# ucar.net
KiCad netlist of a schematic drawn in EAGLE
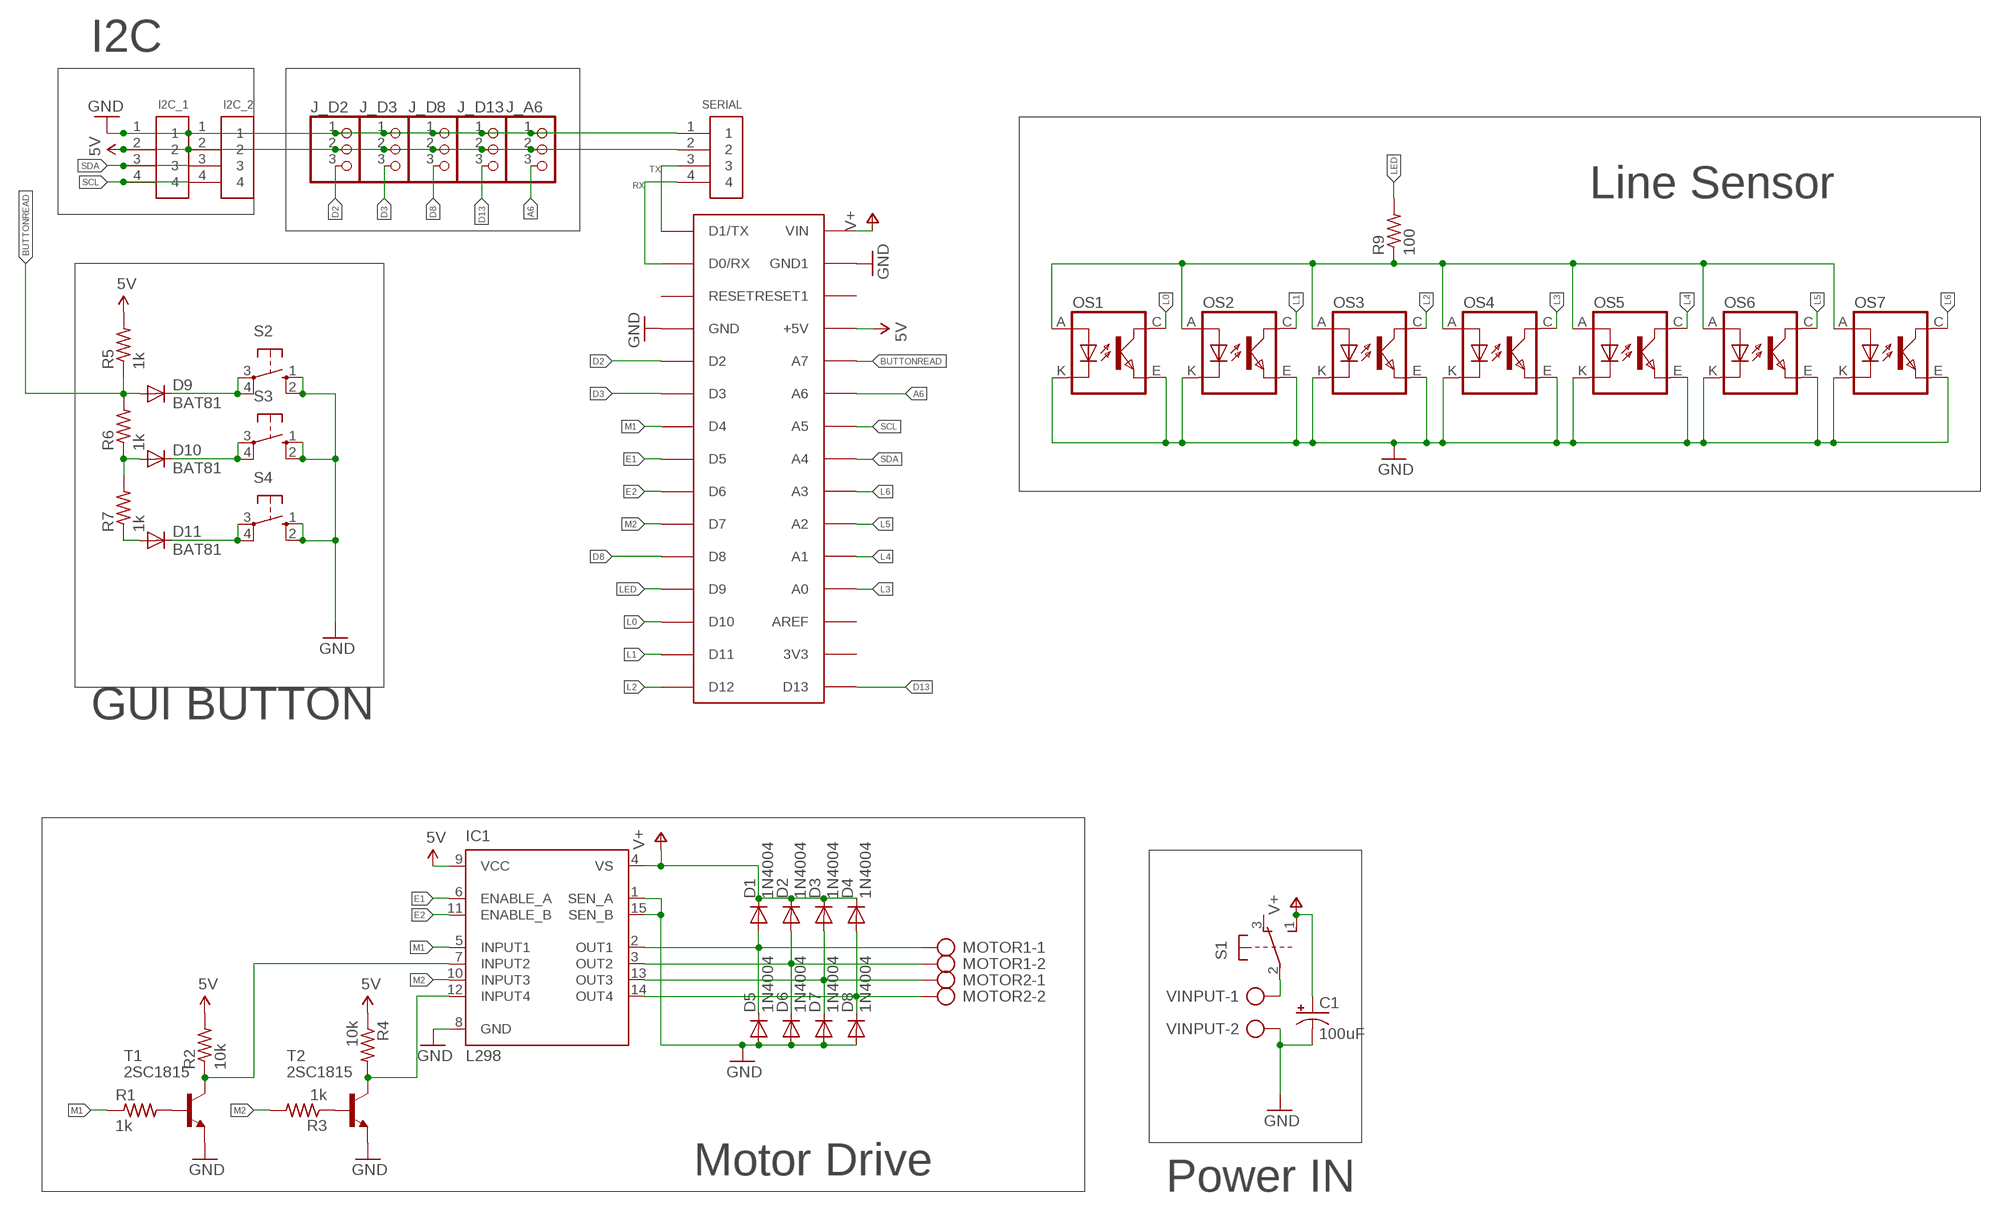
[diagram p0: schematic, sheet 1]

(export (version "E")
  (design (tool "Eeschema 10.0.6"))
  (components
    (comp (ref "C1")
      (value "100uF")
      (footprint "eagle-import:E2,5-6")
      (libsource (lib "eagle-import") (part "CPOL-USE2.5-6"))
    )
    (comp (ref "D1")
      (value "1N4004")
      (footprint "eagle-import:DO41-10")
      (libsource (lib "eagle-import") (part "1N4004"))
    )
    (comp (ref "D2")
      (value "1N4004")
      (footprint "eagle-import:DO41-10")
      (libsource (lib "eagle-import") (part "1N4004"))
    )
    (comp (ref "D3")
      (value "1N4004")
      (footprint "eagle-import:DO41-10")
      (libsource (lib "eagle-import") (part "1N4004"))
    )
    (comp (ref "D4")
      (value "1N4004")
      (footprint "eagle-import:DO41-10")
      (libsource (lib "eagle-import") (part "1N4004"))
    )
    (comp (ref "D5")
      (value "1N4004")
      (footprint "eagle-import:DO41-10")
      (libsource (lib "eagle-import") (part "1N4004"))
    )
    (comp (ref "D6")
      (value "1N4004")
      (footprint "eagle-import:DO41-10")
      (libsource (lib "eagle-import") (part "1N4004"))
    )
    (comp (ref "D7")
      (value "1N4004")
      (footprint "eagle-import:DO41-10")
      (libsource (lib "eagle-import") (part "1N4004"))
    )
    (comp (ref "D8")
      (value "1N4004")
      (footprint "eagle-import:DO41-10")
      (libsource (lib "eagle-import") (part "1N4004"))
    )
    (comp (ref "D9")
      (value "BAT81")
      (footprint "eagle-import:DO34-7")
      (libsource (lib "eagle-import") (part "BAT81"))
    )
    (comp (ref "D10")
      (value "BAT81")
      (footprint "eagle-import:DO34-7")
      (libsource (lib "eagle-import") (part "BAT81"))
    )
    (comp (ref "D11")
      (value "BAT81")
      (footprint "eagle-import:DO34-7")
      (libsource (lib "eagle-import") (part "BAT81"))
    )
    (comp (ref "I2C_1")
      (value "1X4-BIG")
      (footprint "eagle-import:1X04-BIG")
      (libsource (lib "eagle-import") (part "1X4-BIG"))
    )
    (comp (ref "I2C_2")
      (value "1X4-BIG")
      (footprint "eagle-import:1X04-BIG")
      (libsource (lib "eagle-import") (part "1X4-BIG"))
    )
    (comp (ref "IC1")
      (value "L298")
      (footprint "eagle-import:MULTIWATT-15")
      (fields (field (name "MPN") "L298N"))
      (libsource (lib "eagle-import") (part "L298"))
    )
    (comp (ref "J_A6")
      (value "PINHD-1X3")
      (footprint "eagle-import:1X03")
      (libsource (lib "eagle-import") (part "PINHD-1X3"))
    )
    (comp (ref "J_D2")
      (value "PINHD-1X3")
      (footprint "eagle-import:1X03")
      (libsource (lib "eagle-import") (part "PINHD-1X3"))
    )
    (comp (ref "J_D3")
      (value "PINHD-1X3")
      (footprint "eagle-import:1X03")
      (libsource (lib "eagle-import") (part "PINHD-1X3"))
    )
    (comp (ref "J_D8")
      (value "PINHD-1X3")
      (footprint "eagle-import:1X03")
      (libsource (lib "eagle-import") (part "PINHD-1X3"))
    )
    (comp (ref "J_D13")
      (value "PINHD-1X3")
      (footprint "eagle-import:1X03")
      (libsource (lib "eagle-import") (part "PINHD-1X3"))
    )
    (comp (ref "MOTOR1")
      (value "AK500/2")
      (footprint "eagle-import:AK500_2")
      (libsource (lib "eagle-import") (part "AK500/2"))
    )
    (comp (ref "MOTOR2")
      (value "AK500/2")
      (footprint "eagle-import:AK500_2")
      (libsource (lib "eagle-import") (part "AK500/2"))
    )
    (comp (ref "OS1")
      (value "TCRT5000")
      (footprint "eagle-import:TCRT5000")
      (libsource (lib "eagle-import") (part "TCRT5000"))
    )
    (comp (ref "OS2")
      (value "TCRT5000")
      (footprint "eagle-import:TCRT5000")
      (libsource (lib "eagle-import") (part "TCRT5000"))
    )
    (comp (ref "OS3")
      (value "TCRT5000")
      (footprint "eagle-import:TCRT5000")
      (libsource (lib "eagle-import") (part "TCRT5000"))
    )
    (comp (ref "OS4")
      (value "TCRT5000")
      (footprint "eagle-import:TCRT5000")
      (libsource (lib "eagle-import") (part "TCRT5000"))
    )
    (comp (ref "OS5")
      (value "TCRT5000")
      (footprint "eagle-import:TCRT5000")
      (libsource (lib "eagle-import") (part "TCRT5000"))
    )
    (comp (ref "OS6")
      (value "TCRT5000")
      (footprint "eagle-import:TCRT5000")
      (libsource (lib "eagle-import") (part "TCRT5000"))
    )
    (comp (ref "OS7")
      (value "TCRT5000")
      (footprint "eagle-import:TCRT5000")
      (libsource (lib "eagle-import") (part "TCRT5000"))
    )
    (comp (ref "R1")
      (value "1k")
      (footprint "eagle-import:0207_7")
      (libsource (lib "eagle-import") (part "R-US_0207/7"))
    )
    (comp (ref "R2")
      (value "10k")
      (footprint "eagle-import:0207_7")
      (libsource (lib "eagle-import") (part "R-US_0207/7"))
    )
    (comp (ref "R3")
      (value "1k")
      (footprint "eagle-import:0207_7")
      (libsource (lib "eagle-import") (part "R-US_0207/7"))
    )
    (comp (ref "R4")
      (value "10k")
      (footprint "eagle-import:0207_7")
      (libsource (lib "eagle-import") (part "R-US_0207/7"))
    )
    (comp (ref "R5")
      (value "1k")
      (footprint "eagle-import:0207_7")
      (libsource (lib "eagle-import") (part "resistor_R-US_0207/7"))
    )
    (comp (ref "R6")
      (value "1k")
      (footprint "eagle-import:0207_7")
      (libsource (lib "eagle-import") (part "resistor_R-US_0207/7"))
    )
    (comp (ref "R7")
      (value "1k")
      (footprint "eagle-import:0207_7")
      (libsource (lib "eagle-import") (part "resistor_R-US_0207/7"))
    )
    (comp (ref "R9")
      (value "100")
      (footprint "eagle-import:0204_5")
      (libsource (lib "eagle-import") (part "R-US_0204/5"))
    )
    (comp (ref "S1")
      (value "9077-2")
      (footprint "eagle-import:9077-2")
      (libsource (lib "eagle-import") (part "9077-2"))
    )
    (comp (ref "S2")
      (value "10-XX")
      (footprint "eagle-import:B3F-10XX")
      (fields (field (name "MPN") "B3F-1000"))
      (libsource (lib "eagle-import") (part "10-XX"))
    )
    (comp (ref "S3")
      (value "10-XX")
      (footprint "eagle-import:B3F-10XX")
      (fields (field (name "MPN") "B3F-1000"))
      (libsource (lib "eagle-import") (part "10-XX"))
    )
    (comp (ref "S4")
      (value "10-XX")
      (footprint "eagle-import:B3F-10XX")
      (fields (field (name "MPN") "B3F-1000"))
      (libsource (lib "eagle-import") (part "10-XX"))
    )
    (comp (ref "SERIAL")
      (value "1X4-BIG")
      (footprint "eagle-import:1X04-BIG")
      (libsource (lib "eagle-import") (part "1X4-BIG"))
    )
    (comp (ref "T1")
      (value "2SC1815")
      (footprint "eagle-import:TO92-ECB")
      (libsource (lib "eagle-import") (part "2SC1815"))
    )
    (comp (ref "T2")
      (value "2SC1815")
      (footprint "eagle-import:TO92-ECB")
      (libsource (lib "eagle-import") (part "2SC1815"))
    )
    (comp (ref "U$1")
      (value "ARDUINONANO")
      (footprint "eagle-import:PDIP-32")
      (libsource (lib "eagle-import") (part "ARDUINONANO"))
    )
    (comp (ref "VINPUT")
      (value "AK500/2")
      (footprint "eagle-import:AK500_2")
      (libsource (lib "eagle-import") (part "AK500/2"))
    )
  )
  (nets
    (net (code "1") (name "/RX") (class "Default")
      (node (ref "SERIAL") (pin "4") (pinfunction "4_4") (pintype "bidirectional"))
      (node (ref "U$1") (pin "D0/RX") (pinfunction "D0/RX_D0/RX") (pintype "bidirectional"))
    )
    (net (code "2") (name "/TX") (class "Default")
      (node (ref "SERIAL") (pin "3") (pinfunction "3_3") (pintype "bidirectional"))
      (node (ref "U$1") (pin "D1/TX") (pinfunction "D1/TX_D1/TX") (pintype "bidirectional"))
    )
    (net (code "3") (name "5V") (class "Default")
      (node (ref "I2C_1") (pin "2") (pinfunction "2_2") (pintype "bidirectional"))
      (node (ref "I2C_2") (pin "2") (pinfunction "2_2") (pintype "bidirectional"))
      (node (ref "IC1") (pin "9") (pinfunction "VCC_9") (pintype "power_in"))
      (node (ref "J_A6") (pin "2") (pinfunction "2_2") (pintype "passive"))
      (node (ref "J_D13") (pin "2") (pinfunction "2_2") (pintype "passive"))
      (node (ref "J_D2") (pin "2") (pinfunction "2_2") (pintype "passive"))
      (node (ref "J_D3") (pin "2") (pinfunction "2_2") (pintype "passive"))
      (node (ref "J_D8") (pin "2") (pinfunction "2_2") (pintype "passive"))
      (node (ref "R2") (pin "2") (pinfunction "2_2") (pintype "passive"))
      (node (ref "R4") (pin "1") (pinfunction "1_1") (pintype "passive"))
      (node (ref "R5") (pin "2") (pinfunction "2_2") (pintype "passive"))
      (node (ref "SERIAL") (pin "2") (pinfunction "2_2") (pintype "bidirectional"))
      (node (ref "U$1") (pin "+5V") (pinfunction "+5V_+5V") (pintype "bidirectional"))
    )
    (net (code "4") (name "A6") (class "Default")
      (node (ref "J_A6") (pin "3") (pinfunction "3_3") (pintype "passive"))
      (node (ref "U$1") (pin "A6") (pinfunction "A6_A6") (pintype "bidirectional"))
    )
    (net (code "5") (name "BUTTONREAD") (class "Default")
      (node (ref "D9") (pin "A") (pinfunction "A_A") (pintype "passive"))
      (node (ref "R5") (pin "1") (pinfunction "1_1") (pintype "passive"))
      (node (ref "R6") (pin "2") (pinfunction "2_2") (pintype "passive"))
      (node (ref "U$1") (pin "A7") (pinfunction "A7_A7") (pintype "bidirectional"))
    )
    (net (code "6") (name "D2") (class "Default")
      (node (ref "J_D2") (pin "3") (pinfunction "3_3") (pintype "passive"))
      (node (ref "U$1") (pin "D2") (pinfunction "D2_D2") (pintype "bidirectional"))
    )
    (net (code "7") (name "D3") (class "Default")
      (node (ref "J_D3") (pin "3") (pinfunction "3_3") (pintype "passive"))
      (node (ref "U$1") (pin "D3") (pinfunction "D3_D3") (pintype "bidirectional"))
    )
    (net (code "8") (name "D8") (class "Default")
      (node (ref "J_D8") (pin "3") (pinfunction "3_3") (pintype "passive"))
      (node (ref "U$1") (pin "D8") (pinfunction "D8_D8") (pintype "bidirectional"))
    )
    (net (code "9") (name "D13") (class "Default")
      (node (ref "J_D13") (pin "3") (pinfunction "3_3") (pintype "passive"))
      (node (ref "U$1") (pin "D13") (pinfunction "D13_D13") (pintype "bidirectional"))
    )
    (net (code "10") (name "E1") (class "Default")
      (node (ref "IC1") (pin "6") (pinfunction "ENABLE_A_6") (pintype "input"))
      (node (ref "U$1") (pin "D5") (pinfunction "D5_D5") (pintype "bidirectional"))
    )
    (net (code "11") (name "E2") (class "Default")
      (node (ref "IC1") (pin "11") (pinfunction "ENABLE_B_11") (pintype "input"))
      (node (ref "U$1") (pin "D6") (pinfunction "D6_D6") (pintype "bidirectional"))
    )
    (net (code "12") (name "GND") (class "Default")
      (node (ref "C1") (pin "-") (pinfunction "-_-") (pintype "passive"))
      (node (ref "D5") (pin "A") (pinfunction "A_A") (pintype "passive"))
      (node (ref "D6") (pin "A") (pinfunction "A_A") (pintype "passive"))
      (node (ref "D7") (pin "A") (pinfunction "A_A") (pintype "passive"))
      (node (ref "D8") (pin "A") (pinfunction "A_A") (pintype "passive"))
      (node (ref "I2C_1") (pin "1") (pinfunction "1_1") (pintype "bidirectional"))
      (node (ref "I2C_2") (pin "1") (pinfunction "1_1") (pintype "bidirectional"))
      (node (ref "IC1") (pin "1") (pinfunction "SEN_A_1") (pintype "input"))
      (node (ref "IC1") (pin "15") (pinfunction "SEN_B_15") (pintype "input"))
      (node (ref "IC1") (pin "8") (pinfunction "GND_8") (pintype "power_in"))
      (node (ref "J_A6") (pin "1") (pinfunction "1_1") (pintype "passive"))
      (node (ref "J_D13") (pin "1") (pinfunction "1_1") (pintype "passive"))
      (node (ref "J_D2") (pin "1") (pinfunction "1_1") (pintype "passive"))
      (node (ref "J_D3") (pin "1") (pinfunction "1_1") (pintype "passive"))
      (node (ref "J_D8") (pin "1") (pinfunction "1_1") (pintype "passive"))
      (node (ref "OS1") (pin "E") (pinfunction "EMITTER_E") (pintype "passive"))
      (node (ref "OS1") (pin "K") (pinfunction "CATHODE_K") (pintype "passive"))
      (node (ref "OS2") (pin "E") (pinfunction "EMITTER_E") (pintype "passive"))
      (node (ref "OS2") (pin "K") (pinfunction "CATHODE_K") (pintype "passive"))
      (node (ref "OS3") (pin "E") (pinfunction "EMITTER_E") (pintype "passive"))
      (node (ref "OS3") (pin "K") (pinfunction "CATHODE_K") (pintype "passive"))
      (node (ref "OS4") (pin "E") (pinfunction "EMITTER_E") (pintype "passive"))
      (node (ref "OS4") (pin "K") (pinfunction "CATHODE_K") (pintype "passive"))
      (node (ref "OS5") (pin "E") (pinfunction "EMITTER_E") (pintype "passive"))
      (node (ref "OS5") (pin "K") (pinfunction "CATHODE_K") (pintype "passive"))
      (node (ref "OS6") (pin "E") (pinfunction "EMITTER_E") (pintype "passive"))
      (node (ref "OS6") (pin "K") (pinfunction "CATHODE_K") (pintype "passive"))
      (node (ref "OS7") (pin "E") (pinfunction "EMITTER_E") (pintype "passive"))
      (node (ref "OS7") (pin "K") (pinfunction "CATHODE_K") (pintype "passive"))
      (node (ref "S2") (pin "1") (pinfunction "S_1") (pintype "passive"))
      (node (ref "S2") (pin "2") (pinfunction "S1_2") (pintype "passive"))
      (node (ref "S3") (pin "1") (pinfunction "S_1") (pintype "passive"))
      (node (ref "S3") (pin "2") (pinfunction "S1_2") (pintype "passive"))
      (node (ref "S4") (pin "1") (pinfunction "S_1") (pintype "passive"))
      (node (ref "S4") (pin "2") (pinfunction "S1_2") (pintype "passive"))
      (node (ref "SERIAL") (pin "1") (pinfunction "1_1") (pintype "bidirectional"))
      (node (ref "T1") (pin "E") (pinfunction "E_E") (pintype "passive"))
      (node (ref "T2") (pin "E") (pinfunction "E_E") (pintype "passive"))
      (node (ref "U$1") (pin "GND") (pinfunction "GND_GND") (pintype "bidirectional"))
      (node (ref "U$1") (pin "GND1") (pinfunction "GND1_GND1") (pintype "bidirectional"))
      (node (ref "VINPUT") (pin "2") (pinfunction "KL_2") (pintype "passive"))
    )
    (net (code "13") (name "L0") (class "Default")
      (node (ref "OS1") (pin "C") (pinfunction "COLLECTOR_C") (pintype "passive"))
      (node (ref "U$1") (pin "D10") (pinfunction "D10_D10") (pintype "bidirectional"))
    )
    (net (code "14") (name "L1") (class "Default")
      (node (ref "OS2") (pin "C") (pinfunction "COLLECTOR_C") (pintype "passive"))
      (node (ref "U$1") (pin "D11") (pinfunction "D11_D11") (pintype "bidirectional"))
    )
    (net (code "15") (name "L2") (class "Default")
      (node (ref "OS3") (pin "C") (pinfunction "COLLECTOR_C") (pintype "passive"))
      (node (ref "U$1") (pin "D12") (pinfunction "D12_D12") (pintype "bidirectional"))
    )
    (net (code "16") (name "L3") (class "Default")
      (node (ref "OS4") (pin "C") (pinfunction "COLLECTOR_C") (pintype "passive"))
      (node (ref "U$1") (pin "A0") (pinfunction "A0_A0") (pintype "bidirectional"))
    )
    (net (code "17") (name "L4") (class "Default")
      (node (ref "OS5") (pin "C") (pinfunction "COLLECTOR_C") (pintype "passive"))
      (node (ref "U$1") (pin "A1") (pinfunction "A1_A1") (pintype "bidirectional"))
    )
    (net (code "18") (name "L5") (class "Default")
      (node (ref "OS6") (pin "C") (pinfunction "COLLECTOR_C") (pintype "passive"))
      (node (ref "U$1") (pin "A2") (pinfunction "A2_A2") (pintype "bidirectional"))
    )
    (net (code "19") (name "L6") (class "Default")
      (node (ref "OS7") (pin "C") (pinfunction "COLLECTOR_C") (pintype "passive"))
      (node (ref "U$1") (pin "A3") (pinfunction "A3_A3") (pintype "bidirectional"))
    )
    (net (code "20") (name "LED") (class "Default")
      (node (ref "R9") (pin "2") (pinfunction "2_2") (pintype "passive"))
      (node (ref "U$1") (pin "D9") (pinfunction "D9_D9") (pintype "bidirectional"))
    )
    (net (code "21") (name "M1") (class "Default")
      (node (ref "IC1") (pin "5") (pinfunction "INPUT1_5") (pintype "input"))
      (node (ref "R1") (pin "1") (pinfunction "1_1") (pintype "passive"))
      (node (ref "U$1") (pin "D4") (pinfunction "D4_D4") (pintype "bidirectional"))
    )
    (net (code "22") (name "M2") (class "Default")
      (node (ref "IC1") (pin "10") (pinfunction "INPUT3_10") (pintype "input"))
      (node (ref "R3") (pin "2") (pinfunction "2_2") (pintype "passive"))
      (node (ref "U$1") (pin "D7") (pinfunction "D7_D7") (pintype "bidirectional"))
    )
    (net (code "23") (name "Net-(D10-PadA)") (class "Default")
      (node (ref "D10") (pin "A") (pinfunction "A_A") (pintype "passive"))
      (node (ref "R6") (pin "1") (pinfunction "1_1") (pintype "passive"))
      (node (ref "R7") (pin "2") (pinfunction "2_2") (pintype "passive"))
    )
    (net (code "24") (name "Net-(D11-PadA)") (class "Default")
      (node (ref "D11") (pin "A") (pinfunction "A_A") (pintype "passive"))
      (node (ref "R7") (pin "1") (pinfunction "1_1") (pintype "passive"))
    )
    (net (code "25") (name "Net-(IC1-INPUT2)") (class "Default")
      (node (ref "IC1") (pin "7") (pinfunction "INPUT2_7") (pintype "input"))
      (node (ref "R2") (pin "1") (pinfunction "1_1") (pintype "passive"))
      (node (ref "T1") (pin "C") (pinfunction "C_C") (pintype "passive"))
    )
    (net (code "26") (name "Net-(IC1-INPUT4)") (class "Default")
      (node (ref "IC1") (pin "12") (pinfunction "INPUT4_12") (pintype "input"))
      (node (ref "R4") (pin "2") (pinfunction "2_2") (pintype "passive"))
      (node (ref "T2") (pin "C") (pinfunction "C_C") (pintype "passive"))
    )
    (net (code "27") (name "Net-(IC1-OUT1)") (class "Default")
      (node (ref "D1") (pin "A") (pinfunction "A_A") (pintype "passive"))
      (node (ref "D5") (pin "C") (pinfunction "C_C") (pintype "passive"))
      (node (ref "IC1") (pin "2") (pinfunction "OUT1_2") (pintype "output"))
      (node (ref "MOTOR1") (pin "1") (pinfunction "KL_1") (pintype "passive"))
    )
    (net (code "28") (name "Net-(IC1-OUT2)") (class "Default")
      (node (ref "D2") (pin "A") (pinfunction "A_A") (pintype "passive"))
      (node (ref "D6") (pin "C") (pinfunction "C_C") (pintype "passive"))
      (node (ref "IC1") (pin "3") (pinfunction "OUT2_3") (pintype "output"))
      (node (ref "MOTOR1") (pin "2") (pinfunction "KL_2") (pintype "passive"))
    )
    (net (code "29") (name "Net-(IC1-OUT3)") (class "Default")
      (node (ref "D3") (pin "A") (pinfunction "A_A") (pintype "passive"))
      (node (ref "D7") (pin "C") (pinfunction "C_C") (pintype "passive"))
      (node (ref "IC1") (pin "13") (pinfunction "OUT3_13") (pintype "output"))
      (node (ref "MOTOR2") (pin "1") (pinfunction "KL_1") (pintype "passive"))
    )
    (net (code "30") (name "Net-(IC1-OUT4)") (class "Default")
      (node (ref "D4") (pin "A") (pinfunction "A_A") (pintype "passive"))
      (node (ref "D8") (pin "C") (pinfunction "C_C") (pintype "passive"))
      (node (ref "IC1") (pin "14") (pinfunction "OUT4_14") (pintype "output"))
      (node (ref "MOTOR2") (pin "2") (pinfunction "KL_2") (pintype "passive"))
    )
    (net (code "31") (name "Net-(OS1-ANODE)") (class "Default")
      (node (ref "OS1") (pin "A") (pinfunction "ANODE_A") (pintype "passive"))
      (node (ref "OS2") (pin "A") (pinfunction "ANODE_A") (pintype "passive"))
      (node (ref "OS3") (pin "A") (pinfunction "ANODE_A") (pintype "passive"))
      (node (ref "OS4") (pin "A") (pinfunction "ANODE_A") (pintype "passive"))
      (node (ref "OS5") (pin "A") (pinfunction "ANODE_A") (pintype "passive"))
      (node (ref "OS6") (pin "A") (pinfunction "ANODE_A") (pintype "passive"))
      (node (ref "OS7") (pin "A") (pinfunction "ANODE_A") (pintype "passive"))
      (node (ref "R9") (pin "1") (pinfunction "1_1") (pintype "passive"))
    )
    (net (code "32") (name "Net-(R1-Pad2)") (class "Default")
      (node (ref "R1") (pin "2") (pinfunction "2_2") (pintype "passive"))
      (node (ref "T1") (pin "B") (pinfunction "B_B") (pintype "passive"))
    )
    (net (code "33") (name "Net-(R3-Pad1)") (class "Default")
      (node (ref "R3") (pin "1") (pinfunction "1_1") (pintype "passive"))
      (node (ref "T2") (pin "B") (pinfunction "B_B") (pintype "passive"))
    )
    (net (code "34") (name "Net-(S1A-P)") (class "Default")
      (node (ref "S1") (pin "2") (pinfunction "P_2") (pintype "passive"))
      (node (ref "VINPUT") (pin "1") (pinfunction "KL_1") (pintype "passive"))
    )
    (net (code "35") (name "Net-(S2-P)") (class "Default")
      (node (ref "D9") (pin "C") (pinfunction "C_C") (pintype "passive"))
      (node (ref "S2") (pin "3") (pinfunction "P_3") (pintype "passive"))
      (node (ref "S2") (pin "4") (pinfunction "P1_4") (pintype "passive"))
    )
    (net (code "36") (name "Net-(S3-P)") (class "Default")
      (node (ref "D10") (pin "C") (pinfunction "C_C") (pintype "passive"))
      (node (ref "S3") (pin "3") (pinfunction "P_3") (pintype "passive"))
      (node (ref "S3") (pin "4") (pinfunction "P1_4") (pintype "passive"))
    )
    (net (code "37") (name "Net-(S4-P)") (class "Default")
      (node (ref "D11") (pin "C") (pinfunction "C_C") (pintype "passive"))
      (node (ref "S4") (pin "3") (pinfunction "P_3") (pintype "passive"))
      (node (ref "S4") (pin "4") (pinfunction "P1_4") (pintype "passive"))
    )
    (net (code "38") (name "SCL") (class "Default")
      (node (ref "I2C_1") (pin "4") (pinfunction "4_4") (pintype "bidirectional"))
      (node (ref "I2C_2") (pin "4") (pinfunction "4_4") (pintype "bidirectional"))
      (node (ref "U$1") (pin "A5") (pinfunction "A5_A5") (pintype "bidirectional"))
    )
    (net (code "39") (name "SDA") (class "Default")
      (node (ref "I2C_1") (pin "3") (pinfunction "3_3") (pintype "bidirectional"))
      (node (ref "I2C_2") (pin "3") (pinfunction "3_3") (pintype "bidirectional"))
      (node (ref "U$1") (pin "A4") (pinfunction "A4_A4") (pintype "bidirectional"))
    )
    (net (code "40") (name "V+") (class "Default")
      (node (ref "C1") (pin "+") (pinfunction "+_+") (pintype "passive"))
      (node (ref "D1") (pin "C") (pinfunction "C_C") (pintype "passive"))
      (node (ref "D2") (pin "C") (pinfunction "C_C") (pintype "passive"))
      (node (ref "D3") (pin "C") (pinfunction "C_C") (pintype "passive"))
      (node (ref "D4") (pin "C") (pinfunction "C_C") (pintype "passive"))
      (node (ref "IC1") (pin "4") (pinfunction "VS_4") (pintype "power_in"))
      (node (ref "S1") (pin "1") (pinfunction "S_1") (pintype "passive"))
      (node (ref "U$1") (pin "VIN") (pinfunction "VIN_VIN") (pintype "bidirectional"))
    )
    (net (code "41") (name "unconnected-(S1A-O-Pad3)") (class "Default")
      (node (ref "S1") (pin "3") (pinfunction "O_3") (pintype "passive"))
    )
    (net (code "42") (name "unconnected-(U$1-Pad3V3)") (class "Default")
      (node (ref "U$1") (pin "3V3") (pinfunction "3V3_3V3") (pintype "bidirectional"))
    )
    (net (code "43") (name "unconnected-(U$1-PadAREF)") (class "Default")
      (node (ref "U$1") (pin "AREF") (pinfunction "AREF_AREF") (pintype "bidirectional"))
    )
    (net (code "44") (name "unconnected-(U$1-PadRESET)") (class "Default")
      (node (ref "U$1") (pin "RESET") (pinfunction "RESET_RESET") (pintype "bidirectional"))
    )
    (net (code "45") (name "unconnected-(U$1-PadRESET1)") (class "Default")
      (node (ref "U$1") (pin "RESET1") (pinfunction "RESET1_RESET1") (pintype "bidirectional"))
    )
  )
)
